# Power_supplies.net
KiCad netlist of a schematic drawn in Altium Designer
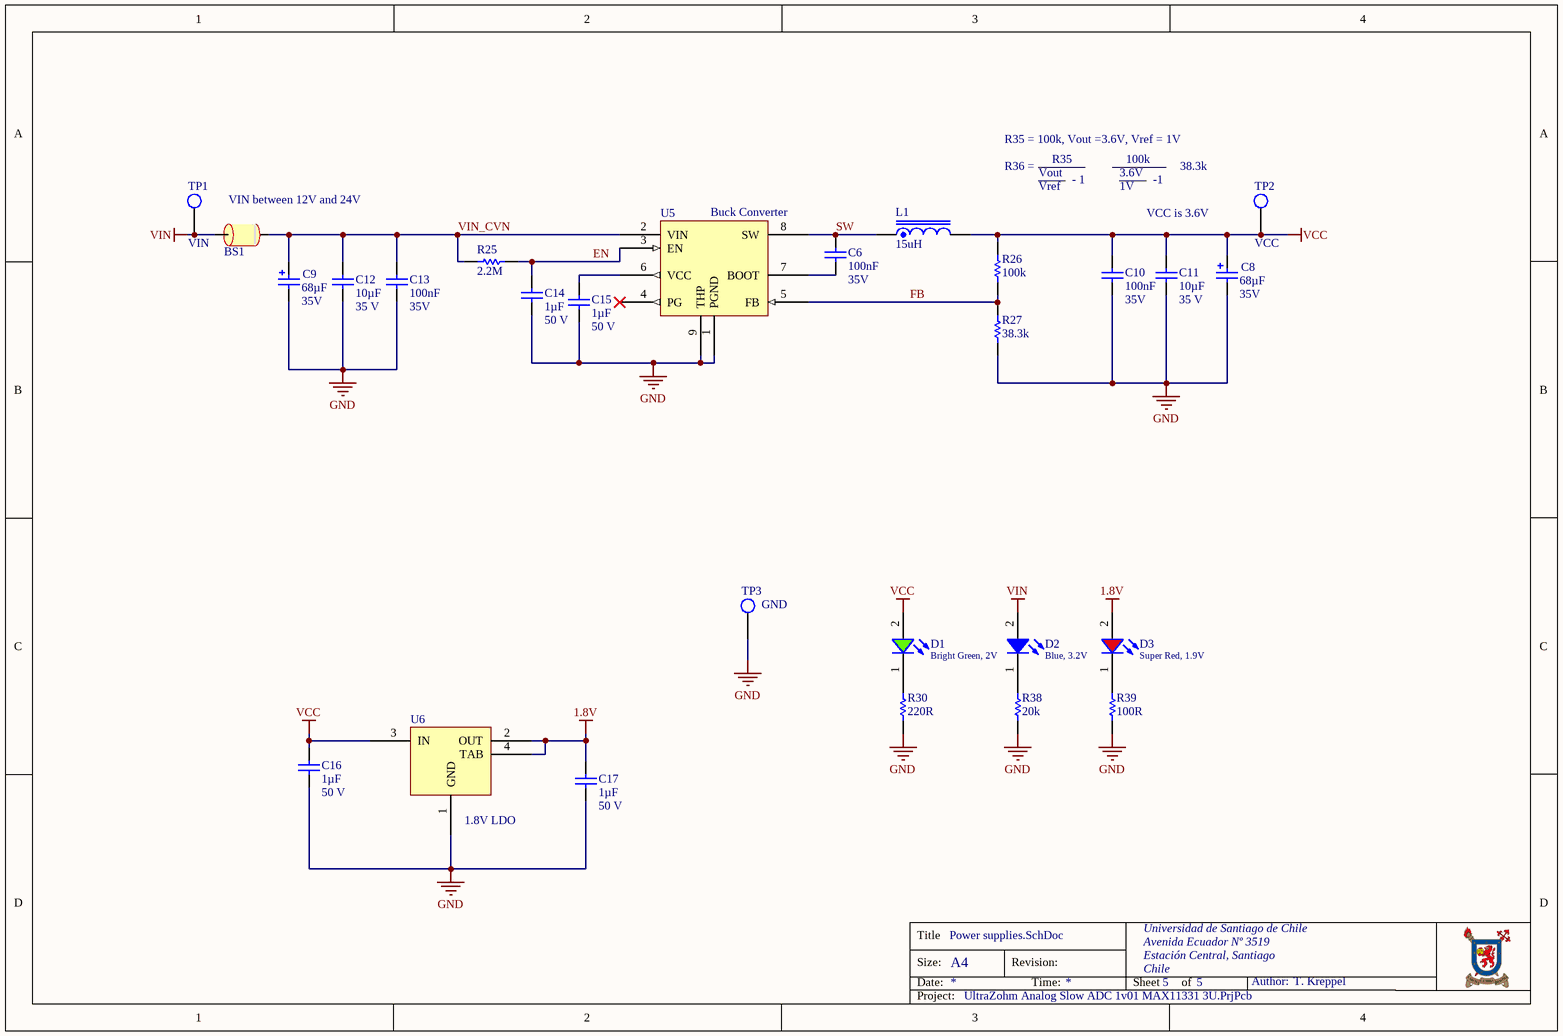
[diagram p0: Power supplies.SchDoc]

(export (version "E")
  (design (tool "Eeschema 10.0.6"))
  (components
    (comp (ref "BS1")
      (value "Ferrite bead")
      (footprint "RES_1206")
      (description "6A")
      (fields (field (name "MPN") "742792121") (field (name "MF") "Würth Elektronik"))
      (libsource (lib "Componentes_SOC") (part "Bead"))
    )
    (comp (ref "C6")
      (value "100nF")
      (footprint "CAP_0603")
      (description "Capacitor")
      (fields
        (field (name "MPN") "C0603C104M5RACTU")
        (field (name "MF") "KEMET")
        (field (name "VOLTAGE") "35V")
        (field (name "PUBLISHER") "Altium Limited")
      )
      (libsource (lib "Componentes_SOC") (part "Cap_0603"))
    )
    (comp (ref "C8")
      (value "68µF")
      (footprint "WCAP-ATG8_6.3x11")
      (description "WCAP-ATG8 THT Aluminum Electrolytic Capacitors, D6.3mm x L11mm, 68uF, +/-20%, 35VDC")
      (fields
        (field (name "PART NUMBER") "860010573006")
        (field (name "TOLERANCE") "+/-20%")
        (field (name "VOLTAGE") "35V")
        (field (name "PUBLISHER") "Wurth Elektronik")
      )
      (libsource (lib "Componentes_SOC") (part "860010573006"))
    )
    (comp (ref "C9")
      (value "68µF")
      (footprint "WCAP-ATG8_6.3x11")
      (description "WCAP-ATG8 THT Aluminum Electrolytic Capacitors, D6.3mm x L11mm, 68uF, +/-20%, 35VDC")
      (fields
        (field (name "PART NUMBER") "860010573006")
        (field (name "TOLERANCE") "+/-20%")
        (field (name "VOLTAGE") "35V")
        (field (name "PUBLISHER") "Wurth Elektronik")
      )
      (libsource (lib "Componentes_SOC") (part "860010573006"))
    )
    (comp (ref "C10")
      (value "100nF")
      (footprint "CAP_0603")
      (description "Capacitor")
      (fields
        (field (name "MPN") "C0603C104M5RACTU")
        (field (name "MF") "KEMET")
        (field (name "VOLTAGE") "35V")
        (field (name "PUBLISHER") "Altium Limited")
      )
      (libsource (lib "Componentes_SOC") (part "Cap_0603"))
    )
    (comp (ref "C11")
      (value "10µF")
      (footprint "RES_1206")
      (description "Capacitor")
      (fields
        (field (name "MPN") "GRM319R6YA106KA12D")
        (field (name "VOLTAGE") "35 V")
        (field (name "TOLERANCE") "10%")
      )
      (libsource (lib "Componentes_SOC") (part "Cap_1206"))
    )
    (comp (ref "C12")
      (value "10µF")
      (footprint "RES_1206")
      (description "Capacitor")
      (fields
        (field (name "MPN") "GRM319R6YA106KA12D")
        (field (name "VOLTAGE") "35 V")
        (field (name "TOLERANCE") "10%")
      )
      (libsource (lib "Componentes_SOC") (part "Cap_1206"))
    )
    (comp (ref "C13")
      (value "100nF")
      (footprint "CAP_0603")
      (description "Capacitor")
      (fields
        (field (name "MPN") "C0603C104M5RACTU")
        (field (name "MF") "KEMET")
        (field (name "VOLTAGE") "35V")
        (field (name "PUBLISHER") "Altium Limited")
      )
      (libsource (lib "Componentes_SOC") (part "Cap_0603"))
    )
    (comp (ref "C14")
      (value "1µF")
      (footprint "CAP_0603")
      (description "Capacitor Ceramic")
      (fields
        (field (name "MPN") "C0603C105K3RACTU")
        (field (name "VOLTAGE") "50 V")
        (field (name "MF") "KEMET")
      )
      (libsource (lib "Componentes_SOC") (part "Cap_0603"))
    )
    (comp (ref "C15")
      (value "1µF")
      (footprint "CAP_0603")
      (description "Capacitor Ceramic")
      (fields
        (field (name "MPN") "C0603C105K3RACTU")
        (field (name "VOLTAGE") "50 V")
        (field (name "MF") "KEMET")
      )
      (libsource (lib "Componentes_SOC") (part "Cap_0603"))
    )
    (comp (ref "C16")
      (value "1µF")
      (footprint "CAP_0603")
      (description "Capacitor Ceramic")
      (fields
        (field (name "MPN") "C0603C105K3RACTU")
        (field (name "VOLTAGE") "50 V")
        (field (name "MF") "KEMET")
      )
      (libsource (lib "Componentes_SOC") (part "Cap_0603"))
    )
    (comp (ref "C17")
      (value "1µF")
      (footprint "CAP_0603")
      (description "Capacitor Ceramic")
      (fields
        (field (name "MPN") "C0603C105K3RACTU")
        (field (name "VOLTAGE") "50 V")
        (field (name "MF") "KEMET")
      )
      (libsource (lib "Componentes_SOC") (part "Cap_0603"))
    )
    (comp (ref "D1")
      (value "Bright Green, 2V")
      (footprint "WL-SMCW_0603_H=0.7mm")
      (description "WL-SMCW SMT Mono-color Chip LED Waterclear, size 0603, Bright Green, 2V, 140deg")
      (fields (field (name "MPN") "150060VS75000") (field (name "MF") "Wurth Elektronik"))
      (libsource (lib "Componentes_SOC") (part "150060VS75000"))
    )
    (comp (ref "D2")
      (value "Blue, 3.2V")
      (footprint "WL-SMCW_0603_H=0.7mm")
      (description "WL-SMCW SMT Mono-color Chip LED Waterclear, size 0603, Blue, 3.2V, 140deg")
      (fields (field (name "MPN") "150060BS75000") (field (name "MF") "Wurth Elektronik"))
      (libsource (lib "Componentes_SOC") (part "150060BS75000"))
    )
    (comp (ref "D3")
      (value "Super Red, 1.9V")
      (footprint "WL-SMCW_0603_H=0.7mm")
      (description "WL-SMCW SMT Mono-color Chip LED Waterclear, size 0603, Super Red, 1.9V, 140deg")
      (fields (field (name "MPN") "150060SS75000") (field (name "MF") "Wurth Elektronik"))
      (libsource (lib "Componentes_SOC") (part "150060SS75000"))
    )
    (comp (ref "L1")
      (value "15uH")
      (footprint "SMT_inductor_1050_Performance")
      (description "SMT power Inductor, 15uH, 40m DRC")
      (fields (field (name "MF") "Murata") (field (name "LCSC PART NUMBER") "C6818993"))
      (libsource (lib "Componentes_SOC") (part "B82464G4154M"))
    )
    (comp (ref "R25")
      (value "2.2M")
      (footprint "RES_0603")
      (fields
        (field (name "MF") "Yageo")
        (field (name "MPN") "RC0603FR-072M2L")
        (field (name "TOLERANCE") "1%")
        (field (name "PUBLISHER") "Altium Limited")
      )
      (libsource (lib "Componentes_SOC") (part "Res0603"))
    )
    (comp (ref "R26")
      (value "100k")
      (footprint "RES_0603")
      (fields
        (field (name "MF") "Yageo")
        (field (name "MPN") "RC0603FR-07100KL")
        (field (name "TOLERANCE") "1%")
        (field (name "PUBLISHER") "Altium Limited")
      )
      (libsource (lib "Componentes_SOC") (part "Res0603"))
    )
    (comp (ref "R27")
      (value "38.3k")
      (footprint "RES_0603")
      (fields (field (name "TOLERANCE") "1%") (field (name "PUBLISHER") "Altium Limited"))
      (libsource (lib "Componentes_SOC") (part "Res0603"))
    )
    (comp (ref "R30")
      (value "220R")
      (footprint "RES_0603")
      (fields
        (field (name "MPN") "RC0603JR-07220RL")
        (field (name "TOLERANCE") "1%")
        (field (name "LCSC PART NUMBER") "C1226")
        (field (name "PUBLISHER") "Altium Limited")
      )
      (libsource (lib "Componentes_SOC") (part "Res0603"))
    )
    (comp (ref "R38")
      (value "20k")
      (footprint "RES_0603")
      (fields
        (field (name "MPN") "RC0603FR-07330RL")
        (field (name "TOLERANCE") "1%")
        (field (name "LCSC PART NUMBER") "C4184")
        (field (name "PUBLISHER") "Altium Limited")
      )
      (libsource (lib "Componentes_SOC") (part "Res0603"))
    )
    (comp (ref "R39")
      (value "100R")
      (footprint "RES_0603")
      (fields
        (field (name "TOLERANCE") "1%")
        (field (name "LCSC PART NUMBER") "C22775")
        (field (name "PUBLISHER") "Altium Limited")
      )
      (libsource (lib "Componentes_SOC") (part "Res0603"))
    )
    (comp (ref "TP1")
      (value "VIN")
      (footprint "TP_1.6mm")
      (description "1.6mm Test Point Keystone")
      (fields
        (field (name "MF") "Keystone Electronics")
        (field (name "MPN") "5006")
        (field (name "CREATED") "2020_04_Kreppel")
      )
      (libsource (lib "Componentes_SOC") (part "TP"))
    )
    (comp (ref "TP2")
      (value "VCC")
      (footprint "TP_1.6mm")
      (description "1.6mm Test Point Keystone")
      (fields
        (field (name "MF") "Keystone Electronics")
        (field (name "MPN") "5006")
        (field (name "CREATED") "2020_04_Kreppel")
      )
      (libsource (lib "Componentes_SOC") (part "TP"))
    )
    (comp (ref "TP3")
      (value "GND")
      (footprint "TP_1.6mm")
      (description "1.6mm Test Point Keystone")
      (fields
        (field (name "MF") "Keystone Electronics")
        (field (name "MPN") "5006")
        (field (name "CREATED") "2020_04_Kreppel")
      )
      (libsource (lib "Componentes_SOC") (part "TP"))
    )
    (comp (ref "U5")
      (value "Buck Converter")
      (footprint "SOIC127P600X170_HS-9N")
      (description "3.8V to 36V, 2A synchronous step-down converter")
      (fields
        (field (name "MF") "Texas Instruments")
        (field (name "MPN") "LMR33620ADDA")
        (field (name "CREATED") "4/20 Kreppel")
      )
      (libsource (lib "Componentes_SOC") (part "LMR33620A"))
    )
    (comp (ref "U6")
      (value "1.8V LDO")
      (footprint "SOT230P700X170-4N")
      (description "1A Positive 1.8V Fixed-Voltage Low-Dropout Regulator")
      (fields
        (field (name "MF") "Texas Instruments")
        (field (name "MPN") "TLV1117LV18DCYR")
        (field (name "CREATED") "2020_04_Kreppel")
      )
      (libsource (lib "Componentes_SOC") (part "TLV1117LV18DCYR"))
    )
  )
  (nets
    (net (code "1") (name "/EN") (class "Default")
      (node (ref "C14") (pin "1") (pinfunction "1_1") (pintype "passive"))
      (node (ref "R25") (pin "1") (pinfunction "1_1") (pintype "passive"))
      (node (ref "U5") (pin "3") (pinfunction "EN_3") (pintype "input"))
    )
    (net (code "2") (name "/FB") (class "Default")
      (node (ref "R26") (pin "1") (pinfunction "1_1") (pintype "passive"))
      (node (ref "R27") (pin "2") (pinfunction "2_2") (pintype "passive"))
      (node (ref "U5") (pin "5") (pinfunction "FB_5") (pintype "input"))
    )
    (net (code "3") (name "/SW") (class "Default")
      (node (ref "C6") (pin "1") (pinfunction "1_1") (pintype "passive"))
      (node (ref "L1") (pin "1") (pinfunction "1_1") (pintype "passive"))
      (node (ref "U5") (pin "8") (pinfunction "SW_8") (pintype "power_in"))
    )
    (net (code "4") (name "/VIN_CVN") (class "Default")
      (node (ref "BS1") (pin "2") (pintype "passive"))
      (node (ref "C12") (pin "1") (pinfunction "1_1") (pintype "passive"))
      (node (ref "C13") (pin "1") (pinfunction "1_1") (pintype "passive"))
      (node (ref "C9") (pin "2") (pinfunction "P_2") (pintype "passive"))
      (node (ref "R25") (pin "2") (pinfunction "2_2") (pintype "passive"))
      (node (ref "U5") (pin "2") (pinfunction "VIN_2") (pintype "power_in"))
    )
    (net (code "5") (name "1.8V") (class "Default")
      (node (ref "C17") (pin "1") (pinfunction "1_1") (pintype "passive"))
      (node (ref "D3") (pin "2") (pinfunction "A_2") (pintype "passive"))
      (node (ref "U6") (pin "2") (pinfunction "OUT_2") (pintype "power_in"))
      (node (ref "U6") (pin "4") (pinfunction "TAB_4") (pintype "power_in"))
    )
    (net (code "6") (name "GND") (class "Default")
      (node (ref "C10") (pin "2") (pinfunction "2_2") (pintype "passive"))
      (node (ref "C11") (pin "2") (pinfunction "2_2") (pintype "passive"))
      (node (ref "C12") (pin "2") (pinfunction "2_2") (pintype "passive"))
      (node (ref "C13") (pin "2") (pinfunction "2_2") (pintype "passive"))
      (node (ref "C14") (pin "2") (pinfunction "2_2") (pintype "passive"))
      (node (ref "C15") (pin "2") (pinfunction "2_2") (pintype "passive"))
      (node (ref "C16") (pin "2") (pinfunction "2_2") (pintype "passive"))
      (node (ref "C17") (pin "2") (pinfunction "2_2") (pintype "passive"))
      (node (ref "C8") (pin "1") (pinfunction "N_1") (pintype "passive"))
      (node (ref "C9") (pin "1") (pinfunction "N_1") (pintype "passive"))
      (node (ref "R27") (pin "1") (pinfunction "1_1") (pintype "passive"))
      (node (ref "R30") (pin "1") (pinfunction "1_1") (pintype "passive"))
      (node (ref "R38") (pin "2") (pinfunction "2_2") (pintype "passive"))
      (node (ref "R39") (pin "2") (pinfunction "2_2") (pintype "passive"))
      (node (ref "TP3") (pin "1") (pinfunction "1_1") (pintype "passive"))
      (node (ref "U5") (pin "1") (pinfunction "PGND_1") (pintype "power_in"))
      (node (ref "U5") (pin "9") (pinfunction "THP_9") (pintype "passive"))
      (node (ref "U6") (pin "1") (pinfunction "GND_1") (pintype "power_in"))
    )
    (net (code "7") (name "Net-(D1-K)") (class "Default")
      (node (ref "D1") (pin "1") (pinfunction "K_1") (pintype "passive"))
      (node (ref "R30") (pin "2") (pinfunction "2_2") (pintype "passive"))
    )
    (net (code "8") (name "Net-(D2-K)") (class "Default")
      (node (ref "D2") (pin "1") (pinfunction "K_1") (pintype "passive"))
      (node (ref "R38") (pin "1") (pinfunction "1_1") (pintype "passive"))
    )
    (net (code "9") (name "Net-(D3-K)") (class "Default")
      (node (ref "D3") (pin "1") (pinfunction "K_1") (pintype "passive"))
      (node (ref "R39") (pin "1") (pinfunction "1_1") (pintype "passive"))
    )
    (net (code "10") (name "Net-(U5-BOOT)") (class "Default")
      (node (ref "C6") (pin "2") (pinfunction "2_2") (pintype "passive"))
      (node (ref "U5") (pin "7") (pinfunction "BOOT_7") (pintype "power_in"))
    )
    (net (code "11") (name "Net-(U5-VCC)") (class "Default")
      (node (ref "C15") (pin "1") (pinfunction "1_1") (pintype "passive"))
      (node (ref "U5") (pin "6") (pinfunction "VCC_6") (pintype "output"))
    )
    (net (code "12") (name "VCC") (class "Default")
      (node (ref "C10") (pin "1") (pinfunction "1_1") (pintype "passive"))
      (node (ref "C11") (pin "1") (pinfunction "1_1") (pintype "passive"))
      (node (ref "C16") (pin "1") (pinfunction "1_1") (pintype "passive"))
      (node (ref "C8") (pin "2") (pinfunction "P_2") (pintype "passive"))
      (node (ref "D1") (pin "2") (pinfunction "A_2") (pintype "passive"))
      (node (ref "L1") (pin "2") (pinfunction "2_2") (pintype "passive"))
      (node (ref "R26") (pin "2") (pinfunction "2_2") (pintype "passive"))
      (node (ref "TP2") (pin "1") (pinfunction "1_1") (pintype "passive"))
      (node (ref "U6") (pin "3") (pinfunction "IN_3") (pintype "power_in"))
    )
    (net (code "13") (name "VIN") (class "Default")
      (node (ref "BS1") (pin "1") (pintype "passive"))
      (node (ref "D2") (pin "2") (pinfunction "A_2") (pintype "passive"))
      (node (ref "TP1") (pin "1") (pinfunction "1_1") (pintype "passive"))
    )
    (net (code "14") (name "unconnected-(U5-PG-Pad4)") (class "Default")
      (node (ref "U5") (pin "4") (pinfunction "PG_4") (pintype "output+no_connect"))
    )
  )
)
